# amplificadorv7.net
KiCad netlist of a schematic drawn in EAGLE
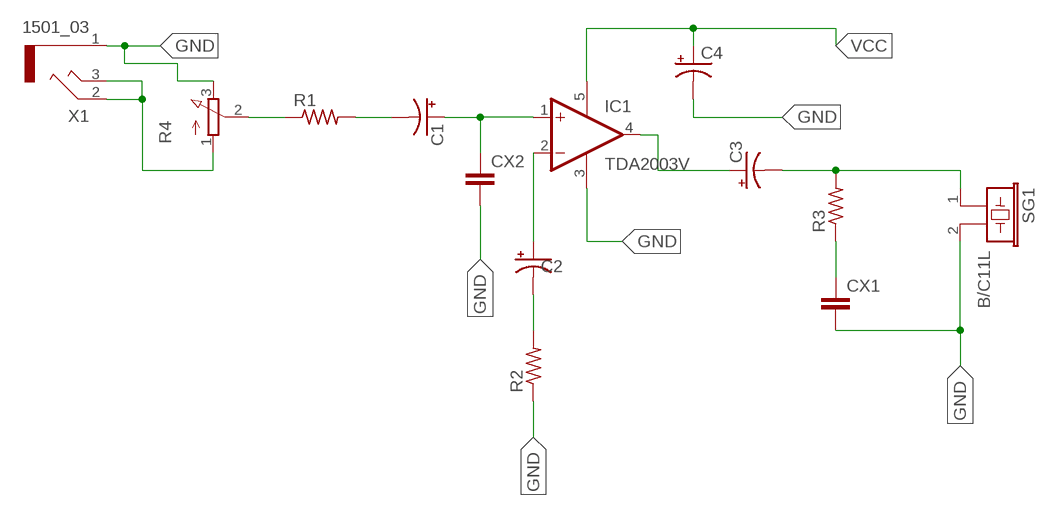
[diagram p0: schematic, sheet 1]

(export (version "E")
  (design (tool "Eeschema 10.0.6"))
  (components
    (comp (ref "C1")
      (value "CPOL-USB45181B")
      (footprint "eagle-import:B45181B")
      (libsource (lib "eagle-import") (part "CPOL-USB45181B"))
    )
    (comp (ref "C2")
      (value "CPOL-USB45181B")
      (footprint "eagle-import:B45181B")
      (libsource (lib "eagle-import") (part "CPOL-USB45181B"))
    )
    (comp (ref "C3")
      (value "CPOL-USB45181B")
      (footprint "eagle-import:B45181B")
      (libsource (lib "eagle-import") (part "CPOL-USB45181B"))
    )
    (comp (ref "C4")
      (value "CPOL-USB45181B")
      (footprint "eagle-import:B45181B")
      (libsource (lib "eagle-import") (part "CPOL-USB45181B"))
    )
    (comp (ref "CX1")
      (value "CXXC10B6")
      (footprint "eagle-import:XC10B6")
      (libsource (lib "eagle-import") (part "CXXC10B6"))
    )
    (comp (ref "CX2")
      (value "CXXC10B6")
      (footprint "eagle-import:XC10B6")
      (libsource (lib "eagle-import") (part "CXXC10B6"))
    )
    (comp (ref "IC1")
      (value "TDA2003V")
      (footprint "eagle-import:CB360")
      (libsource (lib "eagle-import") (part "TDA2003V"))
    )
    (comp (ref "R1")
      (value "R-US_0204/7")
      (footprint "eagle-import:0204_7")
      (libsource (lib "eagle-import") (part "R-US_0204/7"))
    )
    (comp (ref "R2")
      (value "R-US_0204/7")
      (footprint "eagle-import:0204_7")
      (libsource (lib "eagle-import") (part "R-US_0204/7"))
    )
    (comp (ref "R3")
      (value "R-US_0204/7")
      (footprint "eagle-import:0204_7")
      (libsource (lib "eagle-import") (part "R-US_0204/7"))
    )
    (comp (ref "R4")
      (value "3RP/1610N")
      (footprint "eagle-import:3RP_1610N")
      (libsource (lib "eagle-import") (part "3RP/1610N"))
    )
    (comp (ref "SG1")
      (value "B/C11L")
      (footprint "eagle-import:B_C11L")
      (libsource (lib "eagle-import") (part "B/C11L"))
    )
    (comp (ref "X1")
      (value "1501_03")
      (footprint "eagle-import:1501_03")
      (libsource (lib "eagle-import") (part "1501_03"))
    )
  )
  (nets
    (net (code "1") (name "GND") (class "Default")
      (node (ref "C4") (pin "-") (pinfunction "-_-") (pintype "passive"))
      (node (ref "CX1") (pin "2") (pinfunction "2_2") (pintype "passive"))
      (node (ref "CX2") (pin "2") (pinfunction "2_2") (pintype "passive"))
      (node (ref "IC1") (pin "3") (pinfunction "GND_3") (pintype "power_in"))
      (node (ref "R2") (pin "1") (pinfunction "1_1") (pintype "passive"))
      (node (ref "R4") (pin "3") (pinfunction "E_3") (pintype "passive"))
      (node (ref "SG1") (pin "2") (pinfunction "2_2") (pintype "passive"))
      (node (ref "X1") (pin "1") (pinfunction "1_1") (pintype "passive"))
    )
    (net (code "2") (name "Net-(C1-Pad-)") (class "Default")
      (node (ref "C1") (pin "-") (pinfunction "-_-") (pintype "passive"))
      (node (ref "R1") (pin "2") (pinfunction "2_2") (pintype "passive"))
    )
    (net (code "3") (name "Net-(C2-Pad-)") (class "Default")
      (node (ref "C2") (pin "-") (pinfunction "-_-") (pintype "passive"))
      (node (ref "R2") (pin "2") (pinfunction "2_2") (pintype "passive"))
    )
    (net (code "4") (name "Net-(C3-Pad-)") (class "Default")
      (node (ref "C3") (pin "-") (pinfunction "-_-") (pintype "passive"))
      (node (ref "R3") (pin "2") (pinfunction "2_2") (pintype "passive"))
      (node (ref "SG1") (pin "1") (pinfunction "1_1") (pintype "passive"))
    )
    (net (code "5") (name "Net-(CX1-Pad1)") (class "Default")
      (node (ref "CX1") (pin "1") (pinfunction "1_1") (pintype "passive"))
      (node (ref "R3") (pin "1") (pinfunction "1_1") (pintype "passive"))
    )
    (net (code "6") (name "Net-(IC1-+IN)") (class "Default")
      (node (ref "C1") (pin "+") (pinfunction "+_+") (pintype "passive"))
      (node (ref "CX2") (pin "1") (pinfunction "1_1") (pintype "passive"))
      (node (ref "IC1") (pin "1") (pinfunction "+IN_1") (pintype "input"))
    )
    (net (code "7") (name "Net-(IC1--IN)") (class "Default")
      (node (ref "C2") (pin "+") (pinfunction "+_+") (pintype "passive"))
      (node (ref "IC1") (pin "2") (pinfunction "-IN_2") (pintype "input"))
    )
    (net (code "8") (name "Net-(IC1-OUT)") (class "Default")
      (node (ref "C3") (pin "+") (pinfunction "+_+") (pintype "passive"))
      (node (ref "IC1") (pin "4") (pinfunction "OUT_4") (pintype "output"))
    )
    (net (code "9") (name "Net-(R4-A)") (class "Default")
      (node (ref "R4") (pin "1") (pinfunction "A_1") (pintype "passive"))
      (node (ref "X1") (pin "2") (pinfunction "2_2") (pintype "passive"))
      (node (ref "X1") (pin "3") (pinfunction "3_3") (pintype "passive"))
    )
    (net (code "10") (name "Net-(R4-S)") (class "Default")
      (node (ref "R1") (pin "1") (pinfunction "1_1") (pintype "passive"))
      (node (ref "R4") (pin "2") (pinfunction "S_2") (pintype "passive"))
    )
    (net (code "11") (name "VCC") (class "Default")
      (node (ref "C4") (pin "+") (pinfunction "+_+") (pintype "passive"))
      (node (ref "IC1") (pin "5") (pinfunction "V+_5") (pintype "power_in"))
    )
  )
)
